# W501D.net
KiCad netlist of a schematic drawn in EAGLE
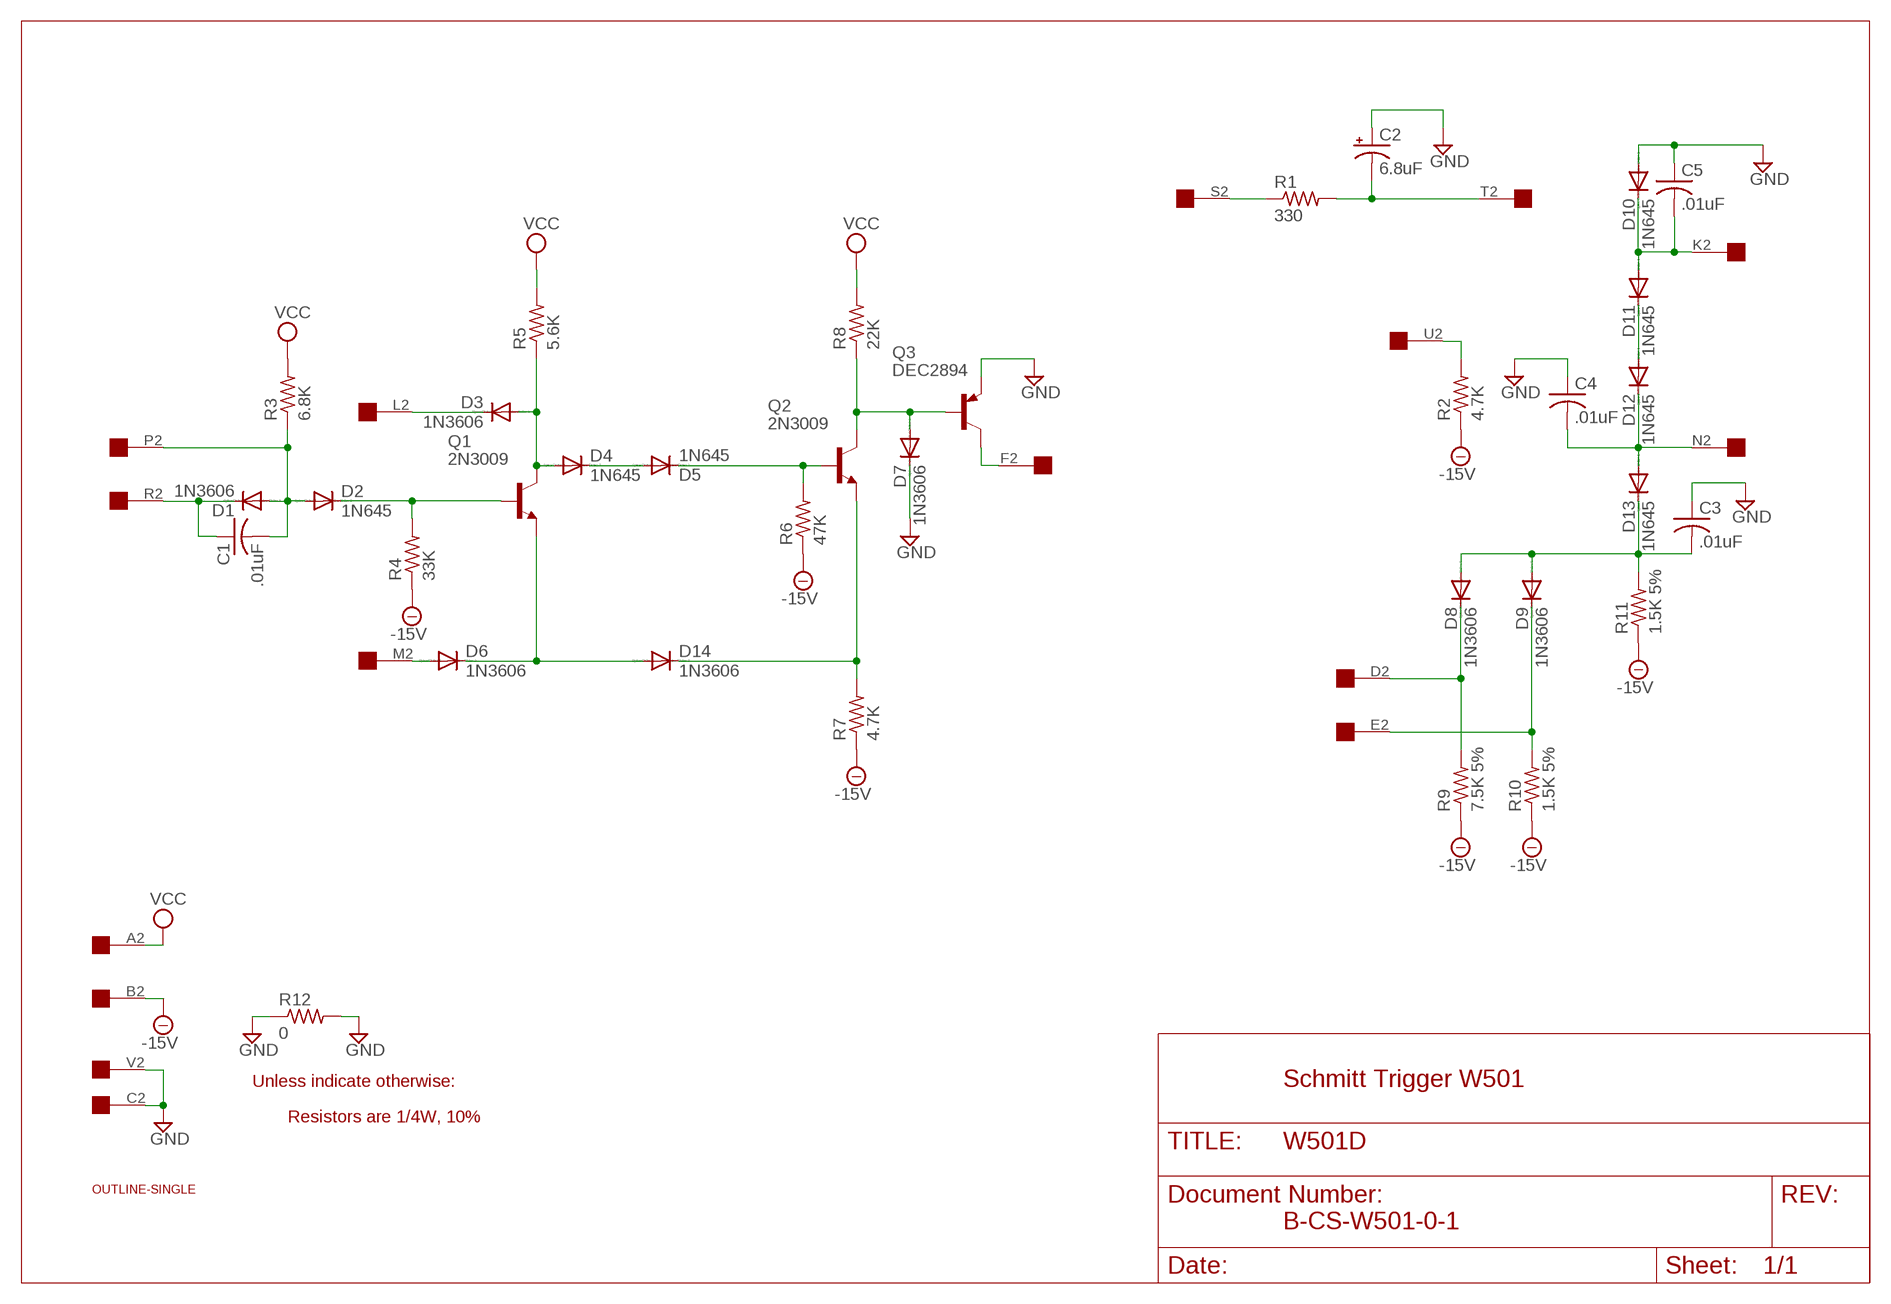
[diagram p0: schematic, sheet 1]

(export (version "E")
  (design (tool "Eeschema 10.0.6"))
  (components
    (comp (ref "C1")
      (value ".01uF")
      (footprint "eagle-import:C075-032X103")
      (libsource (lib "eagle-import") (part "C-US075-032X103"))
    )
    (comp (ref "C2")
      (value "6.8uF")
      (footprint "eagle-import:E12-8")
      (libsource (lib "eagle-import") (part "CPOL-USE20-8AXIAL"))
    )
    (comp (ref "C3")
      (value ".01uF")
      (footprint "eagle-import:C063-025X075")
      (libsource (lib "eagle-import") (part "C-US"))
    )
    (comp (ref "C4")
      (value ".01uF")
      (footprint "eagle-import:C063-025X075")
      (libsource (lib "eagle-import") (part "C-US"))
    )
    (comp (ref "C5")
      (value ".01uF")
      (footprint "eagle-import:C063-025X075")
      (libsource (lib "eagle-import") (part "C-US"))
    )
    (comp (ref "D1")
      (value "1N3606")
      (footprint "eagle-import:DO35-10")
      (libsource (lib "eagle-import") (part "1N4148DO35-10"))
    )
    (comp (ref "D2")
      (value "1N645")
      (footprint "eagle-import:DO35-10")
      (libsource (lib "eagle-import") (part "1N4148DO35-10"))
    )
    (comp (ref "D3")
      (value "1N3606")
      (footprint "eagle-import:DO35-10")
      (libsource (lib "eagle-import") (part "1N4148DO35-10"))
    )
    (comp (ref "D4")
      (value "1N645")
      (footprint "eagle-import:DO35-10")
      (libsource (lib "eagle-import") (part "1N4148DO35-10"))
    )
    (comp (ref "D5")
      (value "1N645")
      (footprint "eagle-import:DO35-10")
      (libsource (lib "eagle-import") (part "1N4148DO35-10"))
    )
    (comp (ref "D6")
      (value "1N3606")
      (footprint "eagle-import:DO35-10")
      (libsource (lib "eagle-import") (part "1N4148DO35-10"))
    )
    (comp (ref "D7")
      (value "1N3606")
      (footprint "eagle-import:DO35-10")
      (libsource (lib "eagle-import") (part "1N4148DO35-10"))
    )
    (comp (ref "D8")
      (value "1N3606")
      (footprint "eagle-import:DO35-10")
      (libsource (lib "eagle-import") (part "1N4148DO35-10"))
    )
    (comp (ref "D9")
      (value "1N3606")
      (footprint "eagle-import:DO35-10")
      (libsource (lib "eagle-import") (part "1N4148DO35-10"))
    )
    (comp (ref "D10")
      (value "1N645")
      (footprint "eagle-import:DO35-10")
      (libsource (lib "eagle-import") (part "1N4148DO35-10"))
    )
    (comp (ref "D11")
      (value "1N645")
      (footprint "eagle-import:DO35-10")
      (libsource (lib "eagle-import") (part "1N4148DO35-10"))
    )
    (comp (ref "D12")
      (value "1N645")
      (footprint "eagle-import:DO35-10")
      (libsource (lib "eagle-import") (part "1N4148DO35-10"))
    )
    (comp (ref "D13")
      (value "1N645")
      (footprint "eagle-import:DO35-10")
      (libsource (lib "eagle-import") (part "1N4148DO35-10"))
    )
    (comp (ref "D14")
      (value "1N3606")
      (footprint "eagle-import:DO35-10")
      (libsource (lib "eagle-import") (part "1N4148DO35-10"))
    )
    (comp (ref "EDGE")
      (value "EDGE-1")
      (footprint "eagle-import:EDGE-CON1")
      (libsource (lib "eagle-import") (part "EDGE-1"))
    )
    (comp (ref "Q1")
      (value "2N3009")
      (footprint "eagle-import:TO5")
      (libsource (lib "eagle-import") (part "2N2102"))
    )
    (comp (ref "Q2")
      (value "2N3009")
      (footprint "eagle-import:TO5")
      (libsource (lib "eagle-import") (part "2N2102"))
    )
    (comp (ref "Q3")
      (value "DEC2894")
      (footprint "eagle-import:TO39")
      (libsource (lib "eagle-import") (part "2N2904"))
    )
    (comp (ref "R1")
      (value "330")
      (footprint "eagle-import:0207_10")
      (libsource (lib "eagle-import") (part "R-US_0207/10"))
    )
    (comp (ref "R2")
      (value "4.7K")
      (footprint "eagle-import:0207_10")
      (libsource (lib "eagle-import") (part "R-US_0207/10"))
    )
    (comp (ref "R3")
      (value "6.8K")
      (footprint "eagle-import:0207_10")
      (libsource (lib "eagle-import") (part "R-US_0207/10"))
    )
    (comp (ref "R4")
      (value "33K")
      (footprint "eagle-import:0207_10")
      (libsource (lib "eagle-import") (part "R-US_0207/10"))
    )
    (comp (ref "R5")
      (value "5.6K")
      (footprint "eagle-import:0207_10")
      (libsource (lib "eagle-import") (part "R-US_0207/10"))
    )
    (comp (ref "R6")
      (value "47K")
      (footprint "eagle-import:0207_10")
      (libsource (lib "eagle-import") (part "R-US_0207/10"))
    )
    (comp (ref "R7")
      (value "4.7K")
      (footprint "eagle-import:0207_10")
      (libsource (lib "eagle-import") (part "R-US_0207/10"))
    )
    (comp (ref "R8")
      (value "22K")
      (footprint "eagle-import:0207_10")
      (libsource (lib "eagle-import") (part "R-US_0207/10"))
    )
    (comp (ref "R9")
      (value "7.5K 5%")
      (footprint "eagle-import:0207_10")
      (libsource (lib "eagle-import") (part "R-US_0207/10"))
    )
    (comp (ref "R10")
      (value "1.5K 5%")
      (footprint "eagle-import:0207_10")
      (libsource (lib "eagle-import") (part "R-US_0207/10"))
    )
    (comp (ref "R11")
      (value "1.5K 5%")
      (footprint "eagle-import:0207_10")
      (libsource (lib "eagle-import") (part "R-US_0207/10"))
    )
    (comp (ref "R12")
      (value "0")
      (footprint "eagle-import:0207_10")
      (libsource (lib "eagle-import") (part "R-US_0207/10"))
    )
    (comp (ref "U$1")
      (value "OUTLINE-SINGLE")
      (footprint "eagle-import:SINGLE")
      (libsource (lib "eagle-import") (part "OUTLINE-SINGLE"))
    )
  )
  (nets
    (net (code "1") (name "-15V") (class "Default")
      (node (ref "EDGE") (pin "B2") (pinfunction "1_B2") (pintype "bidirectional"))
      (node (ref "R10") (pin "1") (pinfunction "1_1") (pintype "passive"))
      (node (ref "R11") (pin "1") (pinfunction "1_1") (pintype "passive"))
      (node (ref "R2") (pin "1") (pinfunction "1_1") (pintype "passive"))
      (node (ref "R4") (pin "1") (pinfunction "1_1") (pintype "passive"))
      (node (ref "R6") (pin "1") (pinfunction "1_1") (pintype "passive"))
      (node (ref "R7") (pin "1") (pinfunction "1_1") (pintype "passive"))
      (node (ref "R9") (pin "1") (pinfunction "1_1") (pintype "passive"))
    )
    (net (code "2") (name "GND") (class "Default")
      (node (ref "C2") (pin "+") (pinfunction "+_+") (pintype "passive"))
      (node (ref "C3") (pin "1") (pinfunction "1_1") (pintype "passive"))
      (node (ref "C4") (pin "1") (pinfunction "1_1") (pintype "passive"))
      (node (ref "C5") (pin "1") (pinfunction "1_1") (pintype "passive"))
      (node (ref "D10") (pin "A") (pinfunction "A_A") (pintype "passive"))
      (node (ref "D7") (pin "C") (pinfunction "C_C") (pintype "passive"))
      (node (ref "EDGE") (pin "C2") (pinfunction "1_C2") (pintype "bidirectional"))
      (node (ref "EDGE") (pin "V2") (pinfunction "1_V2") (pintype "bidirectional"))
      (node (ref "Q3") (pin "1") (pinfunction "E_1") (pintype "passive"))
      (node (ref "R12") (pin "1") (pinfunction "1_1") (pintype "passive"))
      (node (ref "R12") (pin "2") (pinfunction "2_2") (pintype "passive"))
    )
    (net (code "3") (name "Net-(C3-Pad2)") (class "Default")
      (node (ref "C3") (pin "2") (pinfunction "2_2") (pintype "passive"))
      (node (ref "D13") (pin "C") (pinfunction "C_C") (pintype "passive"))
      (node (ref "D8") (pin "A") (pinfunction "A_A") (pintype "passive"))
      (node (ref "D9") (pin "A") (pinfunction "A_A") (pintype "passive"))
      (node (ref "R11") (pin "2") (pinfunction "2_2") (pintype "passive"))
    )
    (net (code "4") (name "Net-(D4-PadC)") (class "Default")
      (node (ref "D4") (pin "C") (pinfunction "C_C") (pintype "passive"))
      (node (ref "D5") (pin "A") (pinfunction "A_A") (pintype "passive"))
    )
    (net (code "5") (name "Net-(D11-PadC)") (class "Default")
      (node (ref "D11") (pin "C") (pinfunction "C_C") (pintype "passive"))
      (node (ref "D12") (pin "A") (pinfunction "A_A") (pintype "passive"))
    )
    (net (code "6") (name "Net-(EDGED-1)") (class "Default")
      (node (ref "D8") (pin "C") (pinfunction "C_C") (pintype "passive"))
      (node (ref "EDGE") (pin "D2") (pinfunction "1_D2") (pintype "bidirectional"))
      (node (ref "R9") (pin "2") (pinfunction "2_2") (pintype "passive"))
    )
    (net (code "7") (name "Net-(EDGEE-1)") (class "Default")
      (node (ref "D9") (pin "C") (pinfunction "C_C") (pintype "passive"))
      (node (ref "EDGE") (pin "E2") (pinfunction "1_E2") (pintype "bidirectional"))
      (node (ref "R10") (pin "2") (pinfunction "2_2") (pintype "passive"))
    )
    (net (code "8") (name "Net-(EDGEF-1)") (class "Default")
      (node (ref "EDGE") (pin "F2") (pinfunction "1_F2") (pintype "bidirectional"))
      (node (ref "Q3") (pin "3") (pinfunction "C_3") (pintype "passive"))
    )
    (net (code "9") (name "Net-(EDGEI-1)") (class "Default")
      (node (ref "C5") (pin "2") (pinfunction "2_2") (pintype "passive"))
      (node (ref "D10") (pin "C") (pinfunction "C_C") (pintype "passive"))
      (node (ref "D11") (pin "A") (pinfunction "A_A") (pintype "passive"))
      (node (ref "EDGE") (pin "K2") (pinfunction "1_K2") (pintype "bidirectional"))
    )
    (net (code "10") (name "Net-(EDGEJ-1)") (class "Default")
      (node (ref "D3") (pin "C") (pinfunction "C_C") (pintype "passive"))
      (node (ref "EDGE") (pin "L2") (pinfunction "1_L2") (pintype "bidirectional"))
    )
    (net (code "11") (name "Net-(EDGEK-1)") (class "Default")
      (node (ref "D6") (pin "A") (pinfunction "A_A") (pintype "passive"))
      (node (ref "EDGE") (pin "M2") (pinfunction "1_M2") (pintype "bidirectional"))
    )
    (net (code "12") (name "Net-(EDGEL-1)") (class "Default")
      (node (ref "C4") (pin "2") (pinfunction "2_2") (pintype "passive"))
      (node (ref "D12") (pin "C") (pinfunction "C_C") (pintype "passive"))
      (node (ref "D13") (pin "A") (pinfunction "A_A") (pintype "passive"))
      (node (ref "EDGE") (pin "N2") (pinfunction "1_N2") (pintype "bidirectional"))
    )
    (net (code "13") (name "Net-(EDGEM-1)") (class "Default")
      (node (ref "C1") (pin "2") (pinfunction "2_2") (pintype "passive"))
      (node (ref "D1") (pin "A") (pinfunction "A_A") (pintype "passive"))
      (node (ref "D2") (pin "A") (pinfunction "A_A") (pintype "passive"))
      (node (ref "EDGE") (pin "P2") (pinfunction "1_P2") (pintype "bidirectional"))
      (node (ref "R3") (pin "1") (pinfunction "1_1") (pintype "passive"))
    )
    (net (code "14") (name "Net-(EDGEN-1)") (class "Default")
      (node (ref "C1") (pin "1") (pinfunction "1_1") (pintype "passive"))
      (node (ref "D1") (pin "C") (pinfunction "C_C") (pintype "passive"))
      (node (ref "EDGE") (pin "R2") (pinfunction "1_R2") (pintype "bidirectional"))
    )
    (net (code "15") (name "Net-(EDGEO-1)") (class "Default")
      (node (ref "EDGE") (pin "S2") (pinfunction "1_S2") (pintype "bidirectional"))
      (node (ref "R1") (pin "1") (pinfunction "1_1") (pintype "passive"))
    )
    (net (code "16") (name "Net-(EDGEP-1)") (class "Default")
      (node (ref "C2") (pin "-") (pinfunction "-_-") (pintype "passive"))
      (node (ref "EDGE") (pin "T2") (pinfunction "1_T2") (pintype "bidirectional"))
      (node (ref "R1") (pin "2") (pinfunction "2_2") (pintype "passive"))
    )
    (net (code "17") (name "Net-(EDGEQ-1)") (class "Default")
      (node (ref "EDGE") (pin "U2") (pinfunction "1_U2") (pintype "bidirectional"))
      (node (ref "R2") (pin "2") (pinfunction "2_2") (pintype "passive"))
    )
    (net (code "18") (name "Net-(Q1-B)") (class "Default")
      (node (ref "D2") (pin "C") (pinfunction "C_C") (pintype "passive"))
      (node (ref "Q1") (pin "2") (pinfunction "B_2") (pintype "passive"))
      (node (ref "R4") (pin "2") (pinfunction "2_2") (pintype "passive"))
    )
    (net (code "19") (name "Net-(Q1-C)") (class "Default")
      (node (ref "D3") (pin "A") (pinfunction "A_A") (pintype "passive"))
      (node (ref "D4") (pin "A") (pinfunction "A_A") (pintype "passive"))
      (node (ref "Q1") (pin "3") (pinfunction "C_3") (pintype "passive"))
      (node (ref "R5") (pin "1") (pinfunction "1_1") (pintype "passive"))
    )
    (net (code "20") (name "Net-(Q1-E)") (class "Default")
      (node (ref "D14") (pin "A") (pinfunction "A_A") (pintype "passive"))
      (node (ref "D6") (pin "C") (pinfunction "C_C") (pintype "passive"))
      (node (ref "Q1") (pin "1") (pinfunction "E_1") (pintype "passive"))
    )
    (net (code "21") (name "Net-(Q2-B)") (class "Default")
      (node (ref "D5") (pin "C") (pinfunction "C_C") (pintype "passive"))
      (node (ref "Q2") (pin "2") (pinfunction "B_2") (pintype "passive"))
      (node (ref "R6") (pin "2") (pinfunction "2_2") (pintype "passive"))
    )
    (net (code "22") (name "Net-(Q2-C)") (class "Default")
      (node (ref "D7") (pin "A") (pinfunction "A_A") (pintype "passive"))
      (node (ref "Q2") (pin "3") (pinfunction "C_3") (pintype "passive"))
      (node (ref "Q3") (pin "2") (pinfunction "B_2") (pintype "passive"))
      (node (ref "R8") (pin "1") (pinfunction "1_1") (pintype "passive"))
    )
    (net (code "23") (name "Net-(Q2-E)") (class "Default")
      (node (ref "D14") (pin "C") (pinfunction "C_C") (pintype "passive"))
      (node (ref "Q2") (pin "1") (pinfunction "E_1") (pintype "passive"))
      (node (ref "R7") (pin "2") (pinfunction "2_2") (pintype "passive"))
    )
    (net (code "24") (name "VCC") (class "Default")
      (node (ref "EDGE") (pin "A2") (pinfunction "1_A2") (pintype "bidirectional"))
      (node (ref "R3") (pin "2") (pinfunction "2_2") (pintype "passive"))
      (node (ref "R5") (pin "2") (pinfunction "2_2") (pintype "passive"))
      (node (ref "R8") (pin "2") (pinfunction "2_2") (pintype "passive"))
    )
  )
)
